# recepteur.net
KiCad netlist of a schematic drawn in EAGLE
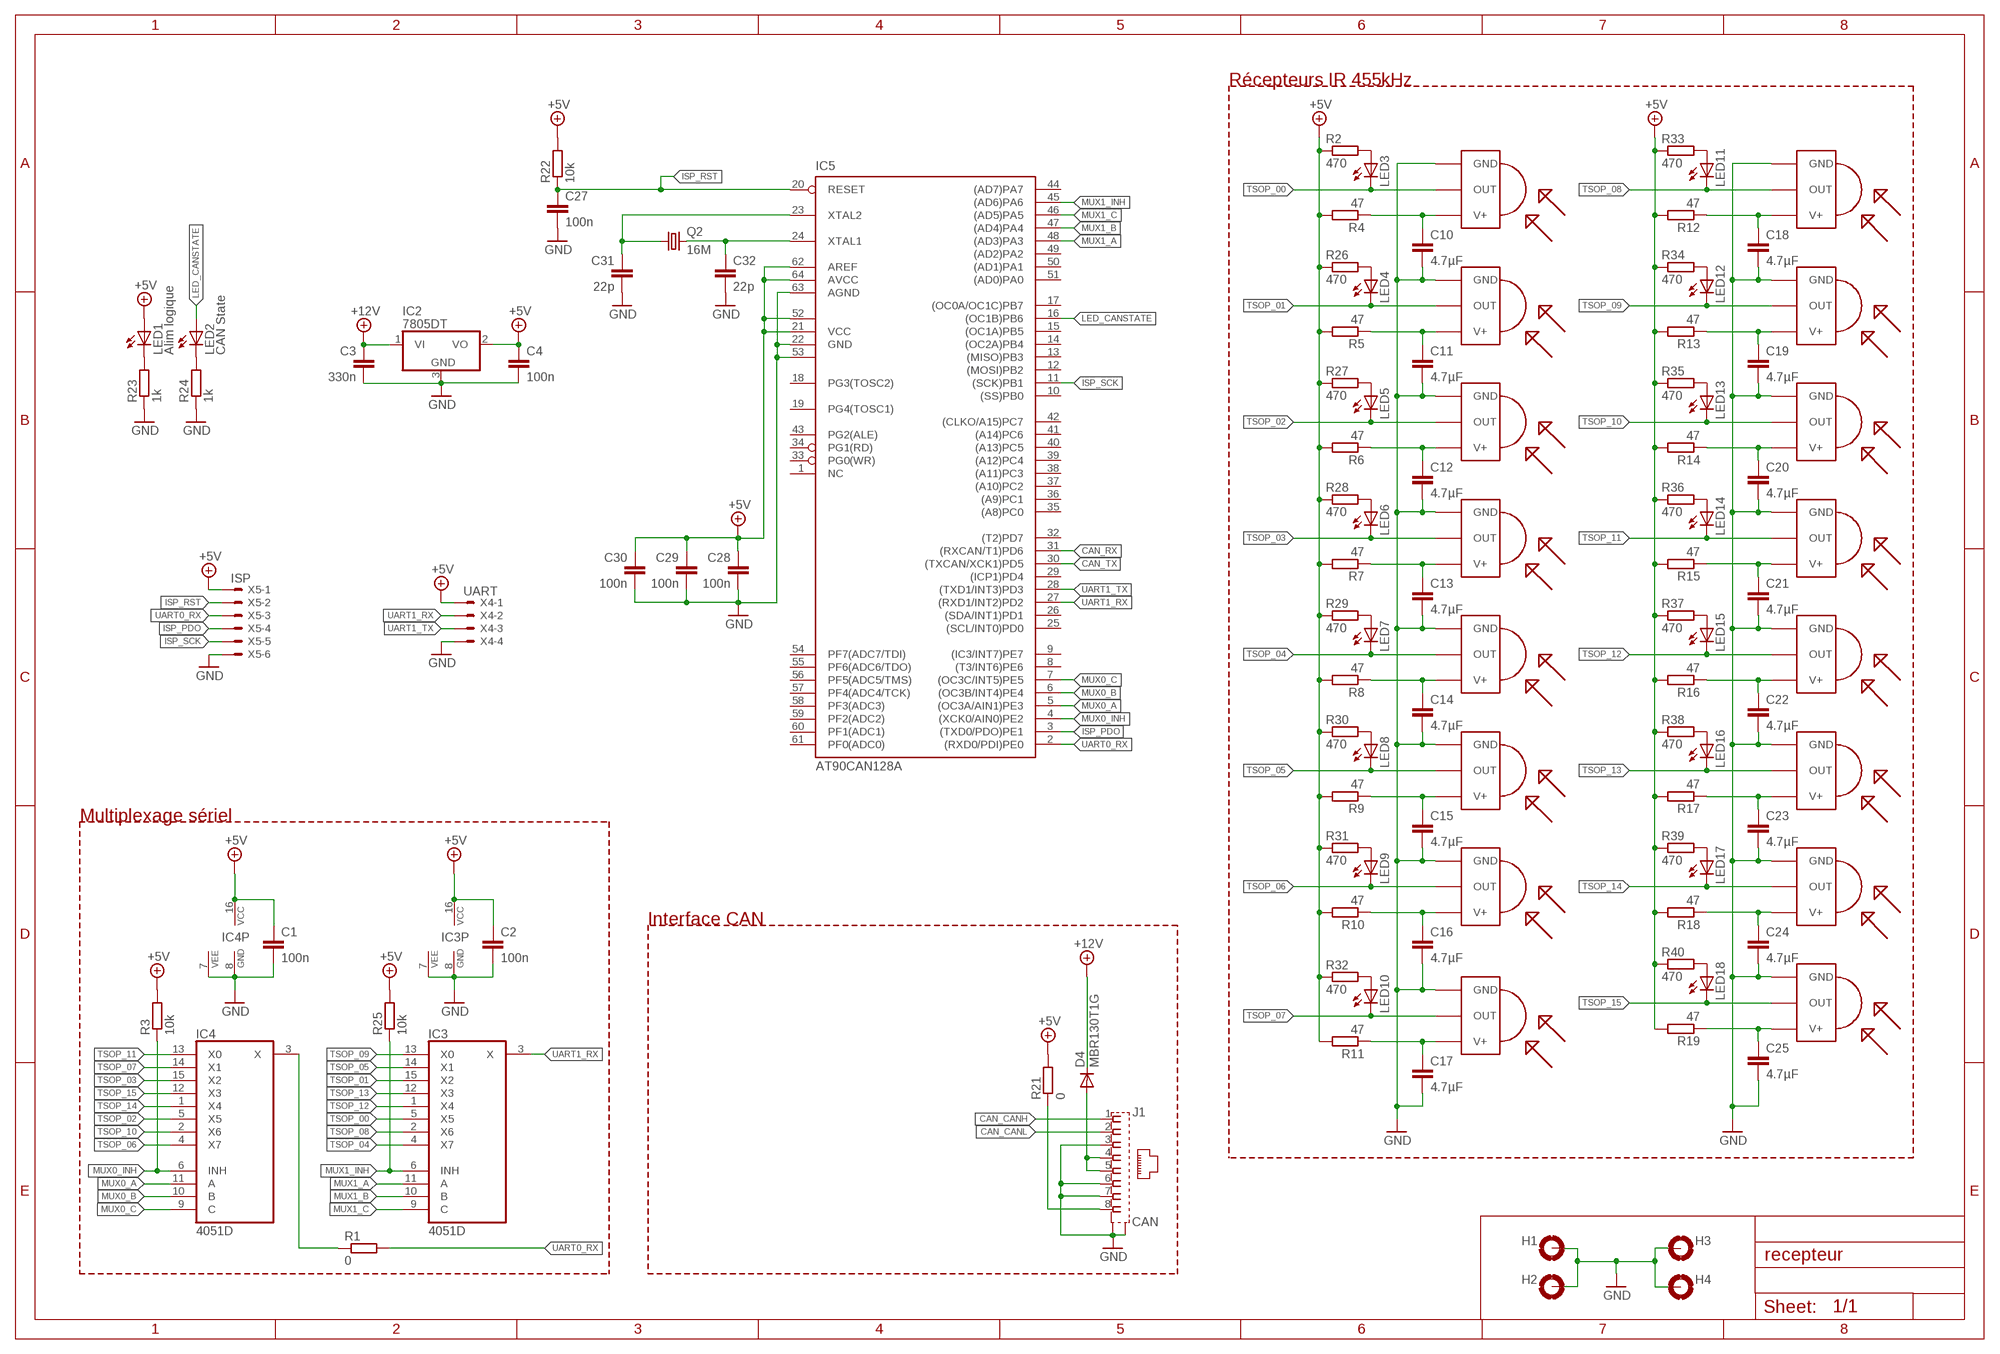
[diagram p0: schematic, sheet 1]

(export (version "E")
  (design (tool "Eeschema 10.0.6"))
  (components
    (comp (ref "C1")
      (value "100n")
      (footprint "eagle-import:C0805")
      (libsource (lib "eagle-import") (part "C-EUC0805"))
    )
    (comp (ref "C2")
      (value "100n")
      (footprint "eagle-import:C0805")
      (libsource (lib "eagle-import") (part "C-EUC0805"))
    )
    (comp (ref "C3")
      (value "330n")
      (footprint "eagle-import:C0805")
      (libsource (lib "eagle-import") (part "C-EUC0805"))
    )
    (comp (ref "C4")
      (value "100n")
      (footprint "eagle-import:C0805")
      (libsource (lib "eagle-import") (part "C-EUC0805"))
    )
    (comp (ref "C10")
      (value "4.7µF")
      (footprint "eagle-import:C0805")
      (libsource (lib "eagle-import") (part "C-EUC0805"))
    )
    (comp (ref "C11")
      (value "4.7µF")
      (footprint "eagle-import:C0805")
      (libsource (lib "eagle-import") (part "C-EUC0805"))
    )
    (comp (ref "C12")
      (value "4.7µF")
      (footprint "eagle-import:C0805")
      (libsource (lib "eagle-import") (part "C-EUC0805"))
    )
    (comp (ref "C13")
      (value "4.7µF")
      (footprint "eagle-import:C0805")
      (libsource (lib "eagle-import") (part "C-EUC0805"))
    )
    (comp (ref "C14")
      (value "4.7µF")
      (footprint "eagle-import:C0805")
      (libsource (lib "eagle-import") (part "C-EUC0805"))
    )
    (comp (ref "C15")
      (value "4.7µF")
      (footprint "eagle-import:C0805")
      (libsource (lib "eagle-import") (part "C-EUC0805"))
    )
    (comp (ref "C16")
      (value "4.7µF")
      (footprint "eagle-import:C0805")
      (libsource (lib "eagle-import") (part "C-EUC0805"))
    )
    (comp (ref "C17")
      (value "4.7µF")
      (footprint "eagle-import:C0805")
      (libsource (lib "eagle-import") (part "C-EUC0805"))
    )
    (comp (ref "C18")
      (value "4.7µF")
      (footprint "eagle-import:C0805")
      (libsource (lib "eagle-import") (part "C-EUC0805"))
    )
    (comp (ref "C19")
      (value "4.7µF")
      (footprint "eagle-import:C0805")
      (libsource (lib "eagle-import") (part "C-EUC0805"))
    )
    (comp (ref "C20")
      (value "4.7µF")
      (footprint "eagle-import:C0805")
      (libsource (lib "eagle-import") (part "C-EUC0805"))
    )
    (comp (ref "C21")
      (value "4.7µF")
      (footprint "eagle-import:C0805")
      (libsource (lib "eagle-import") (part "C-EUC0805"))
    )
    (comp (ref "C22")
      (value "4.7µF")
      (footprint "eagle-import:C0805")
      (libsource (lib "eagle-import") (part "C-EUC0805"))
    )
    (comp (ref "C23")
      (value "4.7µF")
      (footprint "eagle-import:C0805")
      (libsource (lib "eagle-import") (part "C-EUC0805"))
    )
    (comp (ref "C24")
      (value "4.7µF")
      (footprint "eagle-import:C0805")
      (libsource (lib "eagle-import") (part "C-EUC0805"))
    )
    (comp (ref "C25")
      (value "4.7µF")
      (footprint "eagle-import:C0805")
      (libsource (lib "eagle-import") (part "C-EUC0805"))
    )
    (comp (ref "C27")
      (value "100n")
      (footprint "eagle-import:C0805")
      (libsource (lib "eagle-import") (part "C-EUC0805"))
    )
    (comp (ref "C28")
      (value "100n")
      (footprint "eagle-import:C0805")
      (libsource (lib "eagle-import") (part "C-EUC0805"))
    )
    (comp (ref "C29")
      (value "100n")
      (footprint "eagle-import:C0805")
      (libsource (lib "eagle-import") (part "C-EUC0805"))
    )
    (comp (ref "C30")
      (value "100n")
      (footprint "eagle-import:C0805")
      (libsource (lib "eagle-import") (part "C-EUC0805"))
    )
    (comp (ref "C31")
      (value "22p")
      (footprint "eagle-import:C0805")
      (libsource (lib "eagle-import") (part "C-EUC0805"))
    )
    (comp (ref "C32")
      (value "22p")
      (footprint "eagle-import:C0805")
      (libsource (lib "eagle-import") (part "C-EUC0805"))
    )
    (comp (ref "D4")
      (value "MBR130T1G")
      (footprint "eagle-import:SOD123")
      (libsource (lib "eagle-import") (part "DIODE-SOD123"))
    )
    (comp (ref "H1")
      (value "MOUNT-PAD-ROUND3.0")
      (footprint "eagle-import:3,0-PAD")
      (libsource (lib "eagle-import") (part "MOUNT-PAD-ROUND3.0"))
    )
    (comp (ref "H2")
      (value "MOUNT-PAD-ROUND3.0")
      (footprint "eagle-import:3,0-PAD")
      (libsource (lib "eagle-import") (part "MOUNT-PAD-ROUND3.0"))
    )
    (comp (ref "H3")
      (value "MOUNT-PAD-ROUND3.0")
      (footprint "eagle-import:3,0-PAD")
      (libsource (lib "eagle-import") (part "MOUNT-PAD-ROUND3.0"))
    )
    (comp (ref "H4")
      (value "MOUNT-PAD-ROUND3.0")
      (footprint "eagle-import:3,0-PAD")
      (libsource (lib "eagle-import") (part "MOUNT-PAD-ROUND3.0"))
    )
    (comp (ref "IC2")
      (value "7805DT")
      (footprint "eagle-import:TO252")
      (libsource (lib "eagle-import") (part "78DT05"))
    )
    (comp (ref "IC3")
      (value "4051D")
      (footprint "eagle-import:SO16")
      (libsource (lib "eagle-import") (part "4051D"))
    )
    (comp (ref "IC4")
      (value "4051D")
      (footprint "eagle-import:SO16")
      (libsource (lib "eagle-import") (part "4051D"))
    )
    (comp (ref "IC5")
      (value "AT90CAN128A")
      (footprint "eagle-import:TQFP64")
      (libsource (lib "eagle-import") (part "AT90CAN128A"))
    )
    (comp (ref "J1")
      (value "CAN")
      (footprint "eagle-import:557969-1")
      (libsource (lib "eagle-import") (part "557969-1"))
    )
    (comp (ref "LED1")
      (value "Alim logique")
      (footprint "eagle-import:CHIP-LED0805")
      (libsource (lib "eagle-import") (part "LEDCHIP-LED0805"))
    )
    (comp (ref "LED2")
      (value "CAN State")
      (footprint "eagle-import:CHIP-LED0805")
      (libsource (lib "eagle-import") (part "LEDCHIP-LED0805"))
    )
    (comp (ref "LED3")
      (value "LEDCHIP-LED0805")
      (footprint "eagle-import:CHIP-LED0805")
      (libsource (lib "eagle-import") (part "LEDCHIP-LED0805"))
    )
    (comp (ref "LED4")
      (value "LEDCHIP-LED0805")
      (footprint "eagle-import:CHIP-LED0805")
      (libsource (lib "eagle-import") (part "LEDCHIP-LED0805"))
    )
    (comp (ref "LED5")
      (value "LEDCHIP-LED0805")
      (footprint "eagle-import:CHIP-LED0805")
      (libsource (lib "eagle-import") (part "LEDCHIP-LED0805"))
    )
    (comp (ref "LED6")
      (value "LEDCHIP-LED0805")
      (footprint "eagle-import:CHIP-LED0805")
      (libsource (lib "eagle-import") (part "LEDCHIP-LED0805"))
    )
    (comp (ref "LED7")
      (value "LEDCHIP-LED0805")
      (footprint "eagle-import:CHIP-LED0805")
      (libsource (lib "eagle-import") (part "LEDCHIP-LED0805"))
    )
    (comp (ref "LED8")
      (value "LEDCHIP-LED0805")
      (footprint "eagle-import:CHIP-LED0805")
      (libsource (lib "eagle-import") (part "LEDCHIP-LED0805"))
    )
    (comp (ref "LED9")
      (value "LEDCHIP-LED0805")
      (footprint "eagle-import:CHIP-LED0805")
      (libsource (lib "eagle-import") (part "LEDCHIP-LED0805"))
    )
    (comp (ref "LED10")
      (value "LEDCHIP-LED0805")
      (footprint "eagle-import:CHIP-LED0805")
      (libsource (lib "eagle-import") (part "LEDCHIP-LED0805"))
    )
    (comp (ref "LED11")
      (value "LEDCHIP-LED0805")
      (footprint "eagle-import:CHIP-LED0805")
      (libsource (lib "eagle-import") (part "LEDCHIP-LED0805"))
    )
    (comp (ref "LED12")
      (value "LEDCHIP-LED0805")
      (footprint "eagle-import:CHIP-LED0805")
      (libsource (lib "eagle-import") (part "LEDCHIP-LED0805"))
    )
    (comp (ref "LED13")
      (value "LEDCHIP-LED0805")
      (footprint "eagle-import:CHIP-LED0805")
      (libsource (lib "eagle-import") (part "LEDCHIP-LED0805"))
    )
    (comp (ref "LED14")
      (value "LEDCHIP-LED0805")
      (footprint "eagle-import:CHIP-LED0805")
      (libsource (lib "eagle-import") (part "LEDCHIP-LED0805"))
    )
    (comp (ref "LED15")
      (value "LEDCHIP-LED0805")
      (footprint "eagle-import:CHIP-LED0805")
      (libsource (lib "eagle-import") (part "LEDCHIP-LED0805"))
    )
    (comp (ref "LED16")
      (value "LEDCHIP-LED0805")
      (footprint "eagle-import:CHIP-LED0805")
      (libsource (lib "eagle-import") (part "LEDCHIP-LED0805"))
    )
    (comp (ref "LED17")
      (value "LEDCHIP-LED0805")
      (footprint "eagle-import:CHIP-LED0805")
      (libsource (lib "eagle-import") (part "LEDCHIP-LED0805"))
    )
    (comp (ref "LED18")
      (value "LEDCHIP-LED0805")
      (footprint "eagle-import:CHIP-LED0805")
      (libsource (lib "eagle-import") (part "LEDCHIP-LED0805"))
    )
    (comp (ref "Q2")
      (value "16M")
      (footprint "eagle-import:HC49UP")
      (libsource (lib "eagle-import") (part "CRYSTALHC49UP"))
    )
    (comp (ref "R1")
      (value "0")
      (footprint "eagle-import:R0805")
      (libsource (lib "eagle-import") (part "R-EU_R0805"))
    )
    (comp (ref "R2")
      (value "470")
      (footprint "eagle-import:R0805")
      (libsource (lib "eagle-import") (part "R-EU_R0805"))
    )
    (comp (ref "R3")
      (value "10k")
      (footprint "eagle-import:R0805")
      (libsource (lib "eagle-import") (part "R-EU_R0805"))
    )
    (comp (ref "R4")
      (value "47")
      (footprint "eagle-import:R0805")
      (libsource (lib "eagle-import") (part "R-EU_R0805"))
    )
    (comp (ref "R5")
      (value "47")
      (footprint "eagle-import:R0805")
      (libsource (lib "eagle-import") (part "R-EU_R0805"))
    )
    (comp (ref "R6")
      (value "47")
      (footprint "eagle-import:R0805")
      (libsource (lib "eagle-import") (part "R-EU_R0805"))
    )
    (comp (ref "R7")
      (value "47")
      (footprint "eagle-import:R0805")
      (libsource (lib "eagle-import") (part "R-EU_R0805"))
    )
    (comp (ref "R8")
      (value "47")
      (footprint "eagle-import:R0805")
      (libsource (lib "eagle-import") (part "R-EU_R0805"))
    )
    (comp (ref "R9")
      (value "47")
      (footprint "eagle-import:R0805")
      (libsource (lib "eagle-import") (part "R-EU_R0805"))
    )
    (comp (ref "R10")
      (value "47")
      (footprint "eagle-import:R0805")
      (libsource (lib "eagle-import") (part "R-EU_R0805"))
    )
    (comp (ref "R11")
      (value "47")
      (footprint "eagle-import:R0805")
      (libsource (lib "eagle-import") (part "R-EU_R0805"))
    )
    (comp (ref "R12")
      (value "47")
      (footprint "eagle-import:R0805")
      (libsource (lib "eagle-import") (part "R-EU_R0805"))
    )
    (comp (ref "R13")
      (value "47")
      (footprint "eagle-import:R0805")
      (libsource (lib "eagle-import") (part "R-EU_R0805"))
    )
    (comp (ref "R14")
      (value "47")
      (footprint "eagle-import:R0805")
      (libsource (lib "eagle-import") (part "R-EU_R0805"))
    )
    (comp (ref "R15")
      (value "47")
      (footprint "eagle-import:R0805")
      (libsource (lib "eagle-import") (part "R-EU_R0805"))
    )
    (comp (ref "R16")
      (value "47")
      (footprint "eagle-import:R0805")
      (libsource (lib "eagle-import") (part "R-EU_R0805"))
    )
    (comp (ref "R17")
      (value "47")
      (footprint "eagle-import:R0805")
      (libsource (lib "eagle-import") (part "R-EU_R0805"))
    )
    (comp (ref "R18")
      (value "47")
      (footprint "eagle-import:R0805")
      (libsource (lib "eagle-import") (part "R-EU_R0805"))
    )
    (comp (ref "R19")
      (value "47")
      (footprint "eagle-import:R0805")
      (libsource (lib "eagle-import") (part "R-EU_R0805"))
    )
    (comp (ref "R21")
      (value "0")
      (footprint "eagle-import:M0805")
      (libsource (lib "eagle-import") (part "R-EU_M0805"))
    )
    (comp (ref "R22")
      (value "10k")
      (footprint "eagle-import:R0805")
      (libsource (lib "eagle-import") (part "R-EU_R0805"))
    )
    (comp (ref "R23")
      (value "1k")
      (footprint "eagle-import:M0805")
      (libsource (lib "eagle-import") (part "R-EU_M0805"))
    )
    (comp (ref "R24")
      (value "1k")
      (footprint "eagle-import:M0805")
      (libsource (lib "eagle-import") (part "R-EU_M0805"))
    )
    (comp (ref "R25")
      (value "10k")
      (footprint "eagle-import:R0805")
      (libsource (lib "eagle-import") (part "R-EU_R0805"))
    )
    (comp (ref "R26")
      (value "470")
      (footprint "eagle-import:R0805")
      (libsource (lib "eagle-import") (part "R-EU_R0805"))
    )
    (comp (ref "R27")
      (value "470")
      (footprint "eagle-import:R0805")
      (libsource (lib "eagle-import") (part "R-EU_R0805"))
    )
    (comp (ref "R28")
      (value "470")
      (footprint "eagle-import:R0805")
      (libsource (lib "eagle-import") (part "R-EU_R0805"))
    )
    (comp (ref "R29")
      (value "470")
      (footprint "eagle-import:R0805")
      (libsource (lib "eagle-import") (part "R-EU_R0805"))
    )
    (comp (ref "R30")
      (value "470")
      (footprint "eagle-import:R0805")
      (libsource (lib "eagle-import") (part "R-EU_R0805"))
    )
    (comp (ref "R31")
      (value "470")
      (footprint "eagle-import:R0805")
      (libsource (lib "eagle-import") (part "R-EU_R0805"))
    )
    (comp (ref "R32")
      (value "470")
      (footprint "eagle-import:R0805")
      (libsource (lib "eagle-import") (part "R-EU_R0805"))
    )
    (comp (ref "R33")
      (value "470")
      (footprint "eagle-import:R0805")
      (libsource (lib "eagle-import") (part "R-EU_R0805"))
    )
    (comp (ref "R34")
      (value "470")
      (footprint "eagle-import:R0805")
      (libsource (lib "eagle-import") (part "R-EU_R0805"))
    )
    (comp (ref "R35")
      (value "470")
      (footprint "eagle-import:R0805")
      (libsource (lib "eagle-import") (part "R-EU_R0805"))
    )
    (comp (ref "R36")
      (value "470")
      (footprint "eagle-import:R0805")
      (libsource (lib "eagle-import") (part "R-EU_R0805"))
    )
    (comp (ref "R37")
      (value "470")
      (footprint "eagle-import:R0805")
      (libsource (lib "eagle-import") (part "R-EU_R0805"))
    )
    (comp (ref "R38")
      (value "470")
      (footprint "eagle-import:R0805")
      (libsource (lib "eagle-import") (part "R-EU_R0805"))
    )
    (comp (ref "R39")
      (value "470")
      (footprint "eagle-import:R0805")
      (libsource (lib "eagle-import") (part "R-EU_R0805"))
    )
    (comp (ref "R40")
      (value "470")
      (footprint "eagle-import:R0805")
      (libsource (lib "eagle-import") (part "R-EU_R0805"))
    )
    (comp (ref "TSOP00")
      (value "TSOP7000")
      (footprint "eagle-import:TSOP18XX")
      (libsource (lib "eagle-import") (part "TSOP1830"))
    )
    (comp (ref "TSOP01")
      (value "TSOP7000")
      (footprint "eagle-import:TSOP18XX")
      (libsource (lib "eagle-import") (part "TSOP1830"))
    )
    (comp (ref "TSOP02")
      (value "TSOP7000")
      (footprint "eagle-import:TSOP18XX")
      (libsource (lib "eagle-import") (part "TSOP1830"))
    )
    (comp (ref "TSOP03")
      (value "TSOP7000")
      (footprint "eagle-import:TSOP18XX")
      (libsource (lib "eagle-import") (part "TSOP1830"))
    )
    (comp (ref "TSOP04")
      (value "TSOP7000")
      (footprint "eagle-import:TSOP18XX")
      (libsource (lib "eagle-import") (part "TSOP1830"))
    )
    (comp (ref "TSOP05")
      (value "TSOP7000")
      (footprint "eagle-import:TSOP18XX")
      (libsource (lib "eagle-import") (part "TSOP1830"))
    )
    (comp (ref "TSOP06")
      (value "TSOP7000")
      (footprint "eagle-import:TSOP18XX")
      (libsource (lib "eagle-import") (part "TSOP1830"))
    )
    (comp (ref "TSOP07")
      (value "TSOP7000")
      (footprint "eagle-import:TSOP18XX")
      (libsource (lib "eagle-import") (part "TSOP1830"))
    )
    (comp (ref "TSOP08")
      (value "TSOP7000")
      (footprint "eagle-import:TSOP18XX")
      (libsource (lib "eagle-import") (part "TSOP1830"))
    )
    (comp (ref "TSOP09")
      (value "TSOP7000")
      (footprint "eagle-import:TSOP18XX")
      (libsource (lib "eagle-import") (part "TSOP1830"))
    )
    (comp (ref "TSOP10")
      (value "TSOP7000")
      (footprint "eagle-import:TSOP18XX")
      (libsource (lib "eagle-import") (part "TSOP1830"))
    )
    (comp (ref "TSOP11")
      (value "TSOP7000")
      (footprint "eagle-import:TSOP18XX")
      (libsource (lib "eagle-import") (part "TSOP1830"))
    )
    (comp (ref "TSOP12")
      (value "TSOP7000")
      (footprint "eagle-import:TSOP18XX")
      (libsource (lib "eagle-import") (part "TSOP1830"))
    )
    (comp (ref "TSOP13")
      (value "TSOP7000")
      (footprint "eagle-import:TSOP18XX")
      (libsource (lib "eagle-import") (part "TSOP1830"))
    )
    (comp (ref "TSOP14")
      (value "TSOP7000")
      (footprint "eagle-import:TSOP18XX")
      (libsource (lib "eagle-import") (part "TSOP1830"))
    )
    (comp (ref "TSOP15")
      (value "TSOP7000")
      (footprint "eagle-import:TSOP18XX")
      (libsource (lib "eagle-import") (part "TSOP1830"))
    )
    (comp (ref "X4")
      (value "UART")
      (footprint "eagle-import:53261-04")
      (libsource (lib "eagle-import") (part "53?-04261"))
    )
    (comp (ref "X5")
      (value "ISP")
      (footprint "eagle-import:53261-06")
      (libsource (lib "eagle-import") (part "53?-06261"))
    )
  )
  (nets
    (net (code "1") (name "+5V") (class "Default")
      (node (ref "C1") (pin "1") (pinfunction "1_1") (pintype "passive"))
      (node (ref "C2") (pin "1") (pinfunction "1_1") (pintype "passive"))
      (node (ref "C28") (pin "1") (pinfunction "1_1") (pintype "passive"))
      (node (ref "C29") (pin "1") (pinfunction "1_1") (pintype "passive"))
      (node (ref "C30") (pin "1") (pinfunction "1_1") (pintype "passive"))
      (node (ref "C4") (pin "1") (pinfunction "1_1") (pintype "passive"))
      (node (ref "IC2") (pin "2") (pinfunction "VO_2") (pintype "passive"))
      (node (ref "IC3") (pin "16") (pinfunction "VCC_16") (pintype "power_in"))
      (node (ref "IC4") (pin "16") (pinfunction "VCC_16") (pintype "power_in"))
      (node (ref "IC5") (pin "21") (pinfunction "VCC_21") (pintype "power_in"))
      (node (ref "IC5") (pin "52") (pinfunction "VCC1_52") (pintype "power_in"))
      (node (ref "IC5") (pin "62") (pinfunction "AREF_62") (pintype "bidirectional"))
      (node (ref "IC5") (pin "64") (pinfunction "AVCC_64") (pintype "bidirectional"))
      (node (ref "LED1") (pin "A") (pinfunction "A_A") (pintype "passive"))
      (node (ref "R10") (pin "2") (pinfunction "2_2") (pintype "passive"))
      (node (ref "R11") (pin "2") (pinfunction "2_2") (pintype "passive"))
      (node (ref "R12") (pin "2") (pinfunction "2_2") (pintype "passive"))
      (node (ref "R13") (pin "2") (pinfunction "2_2") (pintype "passive"))
      (node (ref "R14") (pin "2") (pinfunction "2_2") (pintype "passive"))
      (node (ref "R15") (pin "2") (pinfunction "2_2") (pintype "passive"))
      (node (ref "R16") (pin "2") (pinfunction "2_2") (pintype "passive"))
      (node (ref "R17") (pin "2") (pinfunction "2_2") (pintype "passive"))
      (node (ref "R18") (pin "2") (pinfunction "2_2") (pintype "passive"))
      (node (ref "R19") (pin "2") (pinfunction "2_2") (pintype "passive"))
      (node (ref "R2") (pin "1") (pinfunction "1_1") (pintype "passive"))
      (node (ref "R21") (pin "2") (pinfunction "2_2") (pintype "passive"))
      (node (ref "R22") (pin "2") (pinfunction "2_2") (pintype "passive"))
      (node (ref "R25") (pin "2") (pinfunction "2_2") (pintype "passive"))
      (node (ref "R26") (pin "1") (pinfunction "1_1") (pintype "passive"))
      (node (ref "R27") (pin "1") (pinfunction "1_1") (pintype "passive"))
      (node (ref "R28") (pin "1") (pinfunction "1_1") (pintype "passive"))
      (node (ref "R29") (pin "1") (pinfunction "1_1") (pintype "passive"))
      (node (ref "R3") (pin "2") (pinfunction "2_2") (pintype "passive"))
      (node (ref "R30") (pin "1") (pinfunction "1_1") (pintype "passive"))
      (node (ref "R31") (pin "1") (pinfunction "1_1") (pintype "passive"))
      (node (ref "R32") (pin "1") (pinfunction "1_1") (pintype "passive"))
      (node (ref "R33") (pin "1") (pinfunction "1_1") (pintype "passive"))
      (node (ref "R34") (pin "1") (pinfunction "1_1") (pintype "passive"))
      (node (ref "R35") (pin "1") (pinfunction "1_1") (pintype "passive"))
      (node (ref "R36") (pin "1") (pinfunction "1_1") (pintype "passive"))
      (node (ref "R37") (pin "1") (pinfunction "1_1") (pintype "passive"))
      (node (ref "R38") (pin "1") (pinfunction "1_1") (pintype "passive"))
      (node (ref "R39") (pin "1") (pinfunction "1_1") (pintype "passive"))
      (node (ref "R4") (pin "2") (pinfunction "2_2") (pintype "passive"))
      (node (ref "R40") (pin "1") (pinfunction "1_1") (pintype "passive"))
      (node (ref "R5") (pin "2") (pinfunction "2_2") (pintype "passive"))
      (node (ref "R6") (pin "2") (pinfunction "2_2") (pintype "passive"))
      (node (ref "R7") (pin "2") (pinfunction "2_2") (pintype "passive"))
      (node (ref "R8") (pin "2") (pinfunction "2_2") (pintype "passive"))
      (node (ref "R9") (pin "2") (pinfunction "2_2") (pintype "passive"))
      (node (ref "X4") (pin "1") (pinfunction "S_1") (pintype "passive"))
      (node (ref "X5") (pin "1") (pinfunction "S_1") (pintype "passive"))
    )
    (net (code "2") (name "+12V") (class "Default")
      (node (ref "C3") (pin "1") (pinfunction "1_1") (pintype "passive"))
      (node (ref "D4") (pin "C") (pinfunction "C_C") (pintype "passive"))
      (node (ref "IC2") (pin "1") (pinfunction "VI_1") (pintype "input"))
    )
    (net (code "3") (name "CAN_CANH") (class "Default")
      (node (ref "J1") (pin "1") (pinfunction "1_1") (pintype "passive"))
    )
    (net (code "4") (name "CAN_CANL") (class "Default")
      (node (ref "J1") (pin "2") (pinfunction "2_2") (pintype "passive"))
    )
    (net (code "5") (name "CAN_RX") (class "Default")
      (node (ref "IC5") (pin "31") (pinfunction "(RXCAN/T1)PD6_31") (pintype "bidirectional"))
    )
    (net (code "6") (name "CAN_TX") (class "Default")
      (node (ref "IC5") (pin "30") (pinfunction "(TXCAN/XCK1)PD5_30") (pintype "bidirectional"))
    )
    (net (code "7") (name "GND") (class "Default")
      (node (ref "C1") (pin "2") (pinfunction "2_2") (pintype "passive"))
      (node (ref "C10") (pin "2") (pinfunction "2_2") (pintype "passive"))
      (node (ref "C11") (pin "2") (pinfunction "2_2") (pintype "passive"))
      (node (ref "C12") (pin "2") (pinfunction "2_2") (pintype "passive"))
      (node (ref "C13") (pin "2") (pinfunction "2_2") (pintype "passive"))
      (node (ref "C14") (pin "2") (pinfunction "2_2") (pintype "passive"))
      (node (ref "C15") (pin "2") (pinfunction "2_2") (pintype "passive"))
      (node (ref "C16") (pin "2") (pinfunction "2_2") (pintype "passive"))
      (node (ref "C17") (pin "2") (pinfunction "2_2") (pintype "passive"))
      (node (ref "C18") (pin "2") (pinfunction "2_2") (pintype "passive"))
      (node (ref "C19") (pin "2") (pinfunction "2_2") (pintype "passive"))
      (node (ref "C2") (pin "2") (pinfunction "2_2") (pintype "passive"))
      (node (ref "C20") (pin "2") (pinfunction "2_2") (pintype "passive"))
      (node (ref "C21") (pin "2") (pinfunction "2_2") (pintype "passive"))
      (node (ref "C22") (pin "2") (pinfunction "2_2") (pintype "passive"))
      (node (ref "C23") (pin "2") (pinfunction "2_2") (pintype "passive"))
      (node (ref "C24") (pin "2") (pinfunction "2_2") (pintype "passive"))
      (node (ref "C25") (pin "2") (pinfunction "2_2") (pintype "passive"))
      (node (ref "C27") (pin "2") (pinfunction "2_2") (pintype "passive"))
      (node (ref "C28") (pin "2") (pinfunction "2_2") (pintype "passive"))
      (node (ref "C29") (pin "2") (pinfunction "2_2") (pintype "passive"))
      (node (ref "C3") (pin "2") (pinfunction "2_2") (pintype "passive"))
      (node (ref "C30") (pin "2") (pinfunction "2_2") (pintype "passive"))
      (node (ref "C31") (pin "2") (pinfunction "2_2") (pintype "passive"))
      (node (ref "C32") (pin "2") (pinfunction "2_2") (pintype "passive"))
      (node (ref "C4") (pin "2") (pinfunction "2_2") (pintype "passive"))
      (node (ref "H1") (pin "B3,0") (pinfunction "MOUNT_B3,0") (pintype "passive"))
      (node (ref "H2") (pin "B3,0") (pinfunction "MOUNT_B3,0") (pintype "passive"))
      (node (ref "H3") (pin "B3,0") (pinfunction "MOUNT_B3,0") (pintype "passive"))
      (node (ref "H4") (pin "B3,0") (pinfunction "MOUNT_B3,0") (pintype "passive"))
      (node (ref "IC2") (pin "3") (pinfunction "GND_3") (pintype "passive"))
      (node (ref "IC3") (pin "7") (pinfunction "VEE_7") (pintype "power_in"))
      (node (ref "IC3") (pin "8") (pinfunction "GND_8") (pintype "power_in"))
      (node (ref "IC4") (pin "7") (pinfunction "VEE_7") (pintype "power_in"))
      (node (ref "IC4") (pin "8") (pinfunction "GND_8") (pintype "power_in"))
      (node (ref "IC5") (pin "22") (pinfunction "GND_22") (pintype "power_in"))
      (node (ref "IC5") (pin "53") (pinfunction "GND1_53") (pintype "power_in"))
      (node (ref "IC5") (pin "63") (pinfunction "AGND_63") (pintype "bidirectional"))
      (node (ref "J1") (pin "3") (pinfunction "3_3") (pintype "passive"))
      (node (ref "J1") (pin "6") (pinfunction "6_6") (pintype "passive"))
      (node (ref "J1") (pin "7") (pinfunction "7_7") (pintype "passive"))
      (node (ref "J1") (pin "G1") (pinfunction "S2_G1") (pintype "passive"))
      (node (ref "J1") (pin "G2") (pinfunction "S1_G2") (pintype "passive"))
      (node (ref "R23") (pin "1") (pinfunction "1_1") (pintype "passive"))
      (node (ref "R24") (pin "1") (pinfunction "1_1") (pintype "passive"))
      (node (ref "TSOP00") (pin "GND") (pinfunction "GND_GND") (pintype "bidirectional"))
      (node (ref "TSOP01") (pin "GND") (pinfunction "GND_GND") (pintype "bidirectional"))
      (node (ref "TSOP02") (pin "GND") (pinfunction "GND_GND") (pintype "bidirectional"))
      (node (ref "TSOP03") (pin "GND") (pinfunction "GND_GND") (pintype "bidirectional"))
      (node (ref "TSOP04") (pin "GND") (pinfunction "GND_GND") (pintype "bidirectional"))
      (node (ref "TSOP05") (pin "GND") (pinfunction "GND_GND") (pintype "bidirectional"))
      (node (ref "TSOP06") (pin "GND") (pinfunction "GND_GND") (pintype "bidirectional"))
      (node (ref "TSOP07") (pin "GND") (pinfunction "GND_GND") (pintype "bidirectional"))
      (node (ref "TSOP08") (pin "GND") (pinfunction "GND_GND") (pintype "bidirectional"))
      (node (ref "TSOP09") (pin "GND") (pinfunction "GND_GND") (pintype "bidirectional"))
      (node (ref "TSOP10") (pin "GND") (pinfunction "GND_GND") (pintype "bidirectional"))
      (node (ref "TSOP11") (pin "GND") (pinfunction "GND_GND") (pintype "bidirectional"))
      (node (ref "TSOP12") (pin "GND") (pinfunction "GND_GND") (pintype "bidirectional"))
      (node (ref "TSOP13") (pin "GND") (pinfunction "GND_GND") (pintype "bidirectional"))
      (node (ref "TSOP14") (pin "GND") (pinfunction "GND_GND") (pintype "bidirectional"))
      (node (ref "TSOP15") (pin "GND") (pinfunction "GND_GND") (pintype "bidirectional"))
      (node (ref "X4") (pin "4") (pinfunction "S_4") (pintype "passive"))
      (node (ref "X5") (pin "6") (pinfunction "S_6") (pintype "passive"))
    )
    (net (code "8") (name "ISP_PDO") (class "Default")
      (node (ref "IC5") (pin "3") (pinfunction "(TXD0/PDO)PE1_3") (pintype "bidirectional"))
      (node (ref "X5") (pin "4") (pinfunction "S_4") (pintype "passive"))
    )
    (net (code "9") (name "ISP_RST") (class "Default")
      (node (ref "C27") (pin "1") (pinfunction "1_1") (pintype "passive"))
      (node (ref "IC5") (pin "20") (pinfunction "RESET_20") (pintype "input"))
      (node (ref "R22") (pin "1") (pinfunction "1_1") (pintype "passive"))
      (node (ref "X5") (pin "2") (pinfunction "S_2") (pintype "passive"))
    )
    (net (code "10") (name "ISP_SCK") (class "Default")
      (node (ref "IC5") (pin "11") (pinfunction "(SCK)PB1_11") (pintype "bidirectional"))
      (node (ref "X5") (pin "5") (pinfunction "S_5") (pintype "passive"))
    )
    (net (code "11") (name "LED_CANSTATE") (class "Default")
      (node (ref "IC5") (pin "16") (pinfunction "(OC1B)PB6_16") (pintype "bidirectional"))
      (node (ref "LED2") (pin "A") (pinfunction "A_A") (pintype "passive"))
    )
    (net (code "12") (name "MUX0_A") (class "Default")
      (node (ref "IC4") (pin "11") (pinfunction "A_11") (pintype "input"))
      (node (ref "IC5") (pin "5") (pinfunction "(OC3A/AIN1)PE3_5") (pintype "bidirectional"))
    )
    (net (code "13") (name "MUX0_B") (class "Default")
      (node (ref "IC4") (pin "10") (pinfunction "B_10") (pintype "input"))
      (node (ref "IC5") (pin "6") (pinfunction "(OC3B/INT4)PE4_6") (pintype "bidirectional"))
    )
    (net (code "14") (name "MUX0_C") (class "Default")
      (node (ref "IC4") (pin "9") (pinfunction "C_9") (pintype "input"))
      (node (ref "IC5") (pin "7") (pinfunction "(OC3C/INT5)PE5_7") (pintype "bidirectional"))
    )
    (net (code "15") (name "MUX0_INH") (class "Default")
      (node (ref "IC4") (pin "6") (pinfunction "INH_6") (pintype "input"))
      (node (ref "IC5") (pin "4") (pinfunction "(XCK0/AIN0)PE2_4") (pintype "bidirectional"))
      (node (ref "R3") (pin "1") (pinfunction "1_1") (pintype "passive"))
    )
    (net (code "16") (name "MUX1_A") (class "Default")
      (node (ref "IC3") (pin "11") (pinfunction "A_11") (pintype "input"))
      (node (ref "IC5") (pin "48") (pinfunction "(AD3)PA3_48") (pintype "bidirectional"))
    )
    (net (code "17") (name "MUX1_B") (class "Default")
      (node (ref "IC3") (pin "10") (pinfunction "B_10") (pintype "input"))
      (node (ref "IC5") (pin "47") (pinfunction "(AD4)PA4_47") (pintype "bidirectional"))
    )
    (net (code "18") (name "MUX1_C") (class "Default")
      (node (ref "IC3") (pin "9") (pinfunction "C_9") (pintype "input"))
      (node (ref "IC5") (pin "46") (pinfunction "(AD5)PA5_46") (pintype "bidirectional"))
    )
    (net (code "19") (name "MUX1_INH") (class "Default")
      (node (ref "IC3") (pin "6") (pinfunction "INH_6") (pintype "input"))
      (node (ref "IC5") (pin "45") (pinfunction "(AD6)PA6_45") (pintype "bidirectional"))
      (node (ref "R25") (pin "1") (pinfunction "1_1") (pintype "passive"))
    )
    (net (code "20") (name "Net-(D4-PadA)") (class "Default")
      (node (ref "D4") (pin "A") (pinfunction "A_A") (pintype "passive"))
      (node (ref "J1") (pin "4") (pinfunction "4_4") (pintype "passive"))
      (node (ref "J1") (pin "5") (pinfunction "5_5") (pintype "passive"))
    )
    (net (code "21") (name "Net-(IC4A-X)") (class "Default")
      (node (ref "IC4") (pin "3") (pinfunction "X_3") (pintype "bidirectional"))
      (node (ref "R1") (pin "1") (pinfunction "1_1") (pintype "passive"))
    )
    (net (code "22") (name "Net-(IC5-XTAL1)") (class "Default")
      (node (ref "C32") (pin "1") (pinfunction "1_1") (pintype "passive"))
      (node (ref "IC5") (pin "24") (pinfunction "XTAL1_24") (pintype "bidirectional"))
      (node (ref "Q2") (pin "2") (pinfunction "2_2") (pintype "passive"))
    )
    (net (code "23") (name "Net-(IC5-XTAL2)") (class "Default")
      (node (ref "C31") (pin "1") (pinfunction "1_1") (pintype "passive"))
      (node (ref "IC5") (pin "23") (pinfunction "XTAL2_23") (pintype "bidirectional"))
      (node (ref "Q2") (pin "1") (pinfunction "1_1") (pintype "passive"))
    )
    (net (code "24") (name "Net-(J1-Pad8)") (class "Default")
      (node (ref "J1") (pin "8") (pinfunction "8_8") (pintype "passive"))
      (node (ref "R21") (pin "1") (pinfunction "1_1") (pintype "passive"))
    )
    (net (code "25") (name "Net-(LED1-PadC)") (class "Default")
      (node (ref "LED1") (pin "C") (pinfunction "C_C") (pintype "passive"))
      (node (ref "R23") (pin "2") (pinfunction "2_2") (pintype "passive"))
    )
    (net (code "26") (name "Net-(LED2-PadC)") (class "Default")
      (node (ref "LED2") (pin "C") (pinfunction "C_C") (pintype "passive"))
      (node (ref "R24") (pin "2") (pinfunction "2_2") (pintype "passive"))
    )
    (net (code "27") (name "Net-(LED3-PadA)") (class "Default")
      (node (ref "LED3") (pin "A") (pinfunction "A_A") (pintype "passive"))
      (node (ref "R2") (pin "2") (pinfunction "2_2") (pintype "passive"))
    )
    (net (code "28") (name "Net-(LED4-PadA)") (class "Default")
      (node (ref "LED4") (pin "A") (pinfunction "A_A") (pintype "passive"))
      (node (ref "R26") (pin "2") (pinfunction "2_2") (pintype "passive"))
    )
    (net (code "29") (name "Net-(LED5-PadA)") (class "Default")
      (node (ref "LED5") (pin "A") (pinfunction "A_A") (pintype "passive"))
      (node (ref "R27") (pin "2") (pinfunction "2_2") (pintype "passive"))
    )
    (net (code "30") (name "Net-(LED6-PadA)") (class "Default")
      (node (ref "LED6") (pin "A") (pinfunction "A_A") (pintype "passive"))
      (node (ref "R28") (pin "2") (pinfunction "2_2") (pintype "passive"))
    )
    (net (code "31") (name "Net-(LED7-PadA)") (class "Default")
      (node (ref "LED7") (pin "A") (pinfunction "A_A") (pintype "passive"))
      (node (ref "R29") (pin "2") (pinfunction "2_2") (pintype "passive"))
    )
    (net (code "32") (name "Net-(LED8-PadA)") (class "Default")
      (node (ref "LED8") (pin "A") (pinfunction "A_A") (pintype "passive"))
      (node (ref "R30") (pin "2") (pinfunction "2_2") (pintype "passive"))
    )
    (net (code "33") (name "Net-(LED9-PadA)") (class "Default")
      (node (ref "LED9") (pin "A") (pinfunction "A_A") (pintype "passive"))
      (node (ref "R31") (pin "2") (pinfunction "2_2") (pintype "passive"))
    )
    (net (code "34") (name "Net-(LED10-PadA)") (class "Default")
      (node (ref "LED10") (pin "A") (pinfunction "A_A") (pintype "passive"))
      (node (ref "R32") (pin "2") (pinfunction "2_2") (pintype "passive"))
    )
    (net (code "35") (name "Net-(LED11-PadA)") (class "Default")
      (node (ref "LED11") (pin "A") (pinfunction "A_A") (pintype "passive"))
      (node (ref "R33") (pin "2") (pinfunction "2_2") (pintype "passive"))
    )
    (net (code "36") (name "Net-(LED12-PadA)") (class "Default")
      (node (ref "LED12") (pin "A") (pinfunction "A_A") (pintype "passive"))
      (node (ref "R34") (pin "2") (pinfunction "2_2") (pintype "passive"))
    )
    (net (code "37") (name "Net-(LED13-PadA)") (class "Default")
      (node (ref "LED13") (pin "A") (pinfunction "A_A") (pintype "passive"))
      (node (ref "R35") (pin "2") (pinfunction "2_2") (pintype "passive"))
    )
    (net (code "38") (name "Net-(LED14-PadA)") (class "Default")
      (node (ref "LED14") (pin "A") (pinfunction "A_A") (pintype "passive"))
      (node (ref "R36") (pin "2") (pinfunction "2_2") (pintype "passive"))
    )
    (net (code "39") (name "Net-(LED15-PadA)") (class "Default")
      (node (ref "LED15") (pin "A") (pinfunction "A_A") (pintype "passive"))
      (node (ref "R37") (pin "2") (pinfunction "2_2") (pintype "passive"))
    )
    (net (code "40") (name "Net-(LED16-PadA)") (class "Default")
      (node (ref "LED16") (pin "A") (pinfunction "A_A") (pintype "passive"))
      (node (ref "R38") (pin "2") (pinfunction "2_2") (pintype "passive"))
    )
    (net (code "41") (name "Net-(LED17-PadA)") (class "Default")
      (node (ref "LED17") (pin "A") (pinfunction "A_A") (pintype "passive"))
      (node (ref "R39") (pin "2") (pinfunction "2_2") (pintype "passive"))
    )
    (net (code "42") (name "Net-(LED18-PadA)") (class "Default")
      (node (ref "LED18") (pin "A") (pinfunction "A_A") (pintype "passive"))
      (node (ref "R40") (pin "2") (pinfunction "2_2") (pintype "passive"))
    )
    (net (code "43") (name "Net-(TSOP00-V+)") (class "Default")
      (node (ref "C10") (pin "1") (pinfunction "1_1") (pintype "passive"))
      (node (ref "R4") (pin "1") (pinfunction "1_1") (pintype "passive"))
      (node (ref "TSOP00") (pin "VCC") (pinfunction "V+_VCC") (pintype "bidirectional"))
    )
    (net (code "44") (name "Net-(TSOP01-V+)") (class "Default")
      (node (ref "C11") (pin "1") (pinfunction "1_1") (pintype "passive"))
      (node (ref "R5") (pin "1") (pinfunction "1_1") (pintype "passive"))
      (node (ref "TSOP01") (pin "VCC") (pinfunction "V+_VCC") (pintype "bidirectional"))
    )
    (net (code "45") (name "Net-(TSOP02-V+)") (class "Default")
      (node (ref "C12") (pin "1") (pinfunction "1_1") (pintype "passive"))
      (node (ref "R6") (pin "1") (pinfunction "1_1") (pintype "passive"))
      (node (ref "TSOP02") (pin "VCC") (pinfunction "V+_VCC") (pintype "bidirectional"))
    )
    (net (code "46") (name "Net-(TSOP03-V+)") (class "Default")
      (node (ref "C13") (pin "1") (pinfunction "1_1") (pintype "passive"))
      (node (ref "R7") (pin "1") (pinfunction "1_1") (pintype "passive"))
      (node (ref "TSOP03") (pin "VCC") (pinfunction "V+_VCC") (pintype "bidirectional"))
    )
    (net (code "47") (name "Net-(TSOP04-V+)") (class "Default")
      (node (ref "C14") (pin "1") (pinfunction "1_1") (pintype "passive"))
      (node (ref "R8") (pin "1") (pinfunction "1_1") (pintype "passive"))
      (node (ref "TSOP04") (pin "VCC") (pinfunction "V+_VCC") (pintype "bidirectional"))
    )
    (net (code "48") (name "Net-(TSOP05-V+)") (class "Default")
      (node (ref "C15") (pin "1") (pinfunction "1_1") (pintype "passive"))
      (node (ref "R9") (pin "1") (pinfunction "1_1") (pintype "passive"))
      (node (ref "TSOP05") (pin "VCC") (pinfunction "V+_VCC") (pintype "bidirectional"))
    )
    (net (code "49") (name "Net-(TSOP06-V+)") (class "Default")
      (node (ref "C16") (pin "1") (pinfunction "1_1") (pintype "passive"))
      (node (ref "R10") (pin "1") (pinfunction "1_1") (pintype "passive"))
      (node (ref "TSOP06") (pin "VCC") (pinfunction "V+_VCC") (pintype "bidirectional"))
    )
    (net (code "50") (name "Net-(TSOP07-V+)") (class "Default")
      (node (ref "C17") (pin "1") (pinfunction "1_1") (pintype "passive"))
      (node (ref "R11") (pin "1") (pinfunction "1_1") (pintype "passive"))
      (node (ref "TSOP07") (pin "VCC") (pinfunction "V+_VCC") (pintype "bidirectional"))
    )
    (net (code "51") (name "Net-(TSOP08-V+)") (class "Default")
      (node (ref "C18") (pin "1") (pinfunction "1_1") (pintype "passive"))
      (node (ref "R12") (pin "1") (pinfunction "1_1") (pintype "passive"))
      (node (ref "TSOP08") (pin "VCC") (pinfunction "V+_VCC") (pintype "bidirectional"))
    )
    (net (code "52") (name "Net-(TSOP09-V+)") (class "Default")
      (node (ref "C19") (pin "1") (pinfunction "1_1") (pintype "passive"))
      (node (ref "R13") (pin "1") (pinfunction "1_1") (pintype "passive"))
      (node (ref "TSOP09") (pin "VCC") (pinfunction "V+_VCC") (pintype "bidirectional"))
    )
    (net (code "53") (name "Net-(TSOP10-V+)") (class "Default")
      (node (ref "C20") (pin "1") (pinfunction "1_1") (pintype "passive"))
      (node (ref "R14") (pin "1") (pinfunction "1_1") (pintype "passive"))
      (node (ref "TSOP10") (pin "VCC") (pinfunction "V+_VCC") (pintype "bidirectional"))
    )
    (net (code "54") (name "Net-(TSOP11-V+)") (class "Default")
      (node (ref "C21") (pin "1") (pinfunction "1_1") (pintype "passive"))
      (node (ref "R15") (pin "1") (pinfunction "1_1") (pintype "passive"))
      (node (ref "TSOP11") (pin "VCC") (pinfunction "V+_VCC") (pintype "bidirectional"))
    )
    (net (code "55") (name "Net-(TSOP12-V+)") (class "Default")
      (node (ref "C22") (pin "1") (pinfunction "1_1") (pintype "passive"))
      (node (ref "R16") (pin "1") (pinfunction "1_1") (pintype "passive"))
      (node (ref "TSOP12") (pin "VCC") (pinfunction "V+_VCC") (pintype "bidirectional"))
    )
    (net (code "56") (name "Net-(TSOP13-V+)") (class "Default")
      (node (ref "C23") (pin "1") (pinfunction "1_1") (pintype "passive"))
      (node (ref "R17") (pin "1") (pinfunction "1_1") (pintype "passive"))
      (node (ref "TSOP13") (pin "VCC") (pinfunction "V+_VCC") (pintype "bidirectional"))
    )
    (net (code "57") (name "Net-(TSOP14-V+)") (class "Default")
      (node (ref "C24") (pin "1") (pinfunction "1_1") (pintype "passive"))
      (node (ref "R18") (pin "1") (pinfunction "1_1") (pintype "passive"))
      (node (ref "TSOP14") (pin "VCC") (pinfunction "V+_VCC") (pintype "bidirectional"))
    )
    (net (code "58") (name "Net-(TSOP15-V+)") (class "Default")
      (node (ref "C25") (pin "1") (pinfunction "1_1") (pintype "passive"))
      (node (ref "R19") (pin "1") (pinfunction "1_1") (pintype "passive"))
      (node (ref "TSOP15") (pin "VCC") (pinfunction "V+_VCC") (pintype "bidirectional"))
    )
    (net (code "59") (name "TSOP_00") (class "Default")
      (node (ref "IC3") (pin "5") (pinfunction "X5_5") (pintype "bidirectional"))
      (node (ref "LED3") (pin "C") (pinfunction "C_C") (pintype "passive"))
      (node (ref "TSOP00") (pin "OUT") (pinfunction "OUT_OUT") (pintype "bidirectional"))
    )
    (net (code "60") (name "TSOP_01") (class "Default")
      (node (ref "IC3") (pin "15") (pinfunction "X2_15") (pintype "bidirectional"))
      (node (ref "LED4") (pin "C") (pinfunction "C_C") (pintype "passive"))
      (node (ref "TSOP01") (pin "OUT") (pinfunction "OUT_OUT") (pintype "bidirectional"))
    )
    (net (code "61") (name "TSOP_02") (class "Default")
      (node (ref "IC4") (pin "5") (pinfunction "X5_5") (pintype "bidirectional"))
      (node (ref "LED5") (pin "C") (pinfunction "C_C") (pintype "passive"))
      (node (ref "TSOP02") (pin "OUT") (pinfunction "OUT_OUT") (pintype "bidirectional"))
    )
    (net (code "62") (name "TSOP_03") (class "Default")
      (node (ref "IC4") (pin "15") (pinfunction "X2_15") (pintype "bidirectional"))
      (node (ref "LED6") (pin "C") (pinfunction "C_C") (pintype "passive"))
      (node (ref "TSOP03") (pin "OUT") (pinfunction "OUT_OUT") (pintype "bidirectional"))
    )
    (net (code "63") (name "TSOP_04") (class "Default")
      (node (ref "IC3") (pin "4") (pinfunction "X7_4") (pintype "bidirectional"))
      (node (ref "LED7") (pin "C") (pinfunction "C_C") (pintype "passive"))
      (node (ref "TSOP04") (pin "OUT") (pinfunction "OUT_OUT") (pintype "bidirectional"))
    )
    (net (code "64") (name "TSOP_05") (class "Default")
      (node (ref "IC3") (pin "14") (pinfunction "X1_14") (pintype "bidirectional"))
      (node (ref "LED8") (pin "C") (pinfunction "C_C") (pintype "passive"))
      (node (ref "TSOP05") (pin "OUT") (pinfunction "OUT_OUT") (pintype "bidirectional"))
    )
    (net (code "65") (name "TSOP_06") (class "Default")
      (node (ref "IC4") (pin "4") (pinfunction "X7_4") (pintype "bidirectional"))
      (node (ref "LED9") (pin "C") (pinfunction "C_C") (pintype "passive"))
      (node (ref "TSOP06") (pin "OUT") (pinfunction "OUT_OUT") (pintype "bidirectional"))
    )
    (net (code "66") (name "TSOP_07") (class "Default")
      (node (ref "IC4") (pin "14") (pinfunction "X1_14") (pintype "bidirectional"))
      (node (ref "LED10") (pin "C") (pinfunction "C_C") (pintype "passive"))
      (node (ref "TSOP07") (pin "OUT") (pinfunction "OUT_OUT") (pintype "bidirectional"))
    )
    (net (code "67") (name "TSOP_08") (class "Default")
      (node (ref "IC3") (pin "2") (pinfunction "X6_2") (pintype "bidirectional"))
      (node (ref "LED11") (pin "C") (pinfunction "C_C") (pintype "passive"))
      (node (ref "TSOP08") (pin "OUT") (pinfunction "OUT_OUT") (pintype "bidirectional"))
    )
    (net (code "68") (name "TSOP_09") (class "Default")
      (node (ref "IC3") (pin "13") (pinfunction "X0_13") (pintype "bidirectional"))
      (node (ref "LED12") (pin "C") (pinfunction "C_C") (pintype "passive"))
      (node (ref "TSOP09") (pin "OUT") (pinfunction "OUT_OUT") (pintype "bidirectional"))
    )
    (net (code "69") (name "TSOP_10") (class "Default")
      (node (ref "IC4") (pin "2") (pinfunction "X6_2") (pintype "bidirectional"))
      (node (ref "LED13") (pin "C") (pinfunction "C_C") (pintype "passive"))
      (node (ref "TSOP10") (pin "OUT") (pinfunction "OUT_OUT") (pintype "bidirectional"))
    )
    (net (code "70") (name "TSOP_11") (class "Default")
      (node (ref "IC4") (pin "13") (pinfunction "X0_13") (pintype "bidirectional"))
      (node (ref "LED14") (pin "C") (pinfunction "C_C") (pintype "passive"))
      (node (ref "TSOP11") (pin "OUT") (pinfunction "OUT_OUT") (pintype "bidirectional"))
    )
    (net (code "71") (name "TSOP_12") (class "Default")
      (node (ref "IC3") (pin "1") (pinfunction "X4_1") (pintype "bidirectional"))
      (node (ref "LED15") (pin "C") (pinfunction "C_C") (pintype "passive"))
      (node (ref "TSOP12") (pin "OUT") (pinfunction "OUT_OUT") (pintype "bidirectional"))
    )
    (net (code "72") (name "TSOP_13") (class "Default")
      (node (ref "IC3") (pin "12") (pinfunction "X3_12") (pintype "bidirectional"))
      (node (ref "LED16") (pin "C") (pinfunction "C_C") (pintype "passive"))
      (node (ref "TSOP13") (pin "OUT") (pinfunction "OUT_OUT") (pintype "bidirectional"))
    )
    (net (code "73") (name "TSOP_14") (class "Default")
      (node (ref "IC4") (pin "1") (pinfunction "X4_1") (pintype "bidirectional"))
      (node (ref "LED17") (pin "C") (pinfunction "C_C") (pintype "passive"))
      (node (ref "TSOP14") (pin "OUT") (pinfunction "OUT_OUT") (pintype "bidirectional"))
    )
    (net (code "74") (name "TSOP_15") (class "Default")
      (node (ref "IC4") (pin "12") (pinfunction "X3_12") (pintype "bidirectional"))
      (node (ref "LED18") (pin "C") (pinfunction "C_C") (pintype "passive"))
      (node (ref "TSOP15") (pin "OUT") (pinfunction "OUT_OUT") (pintype "bidirectional"))
    )
    (net (code "75") (name "UART0_RX") (class "Default")
      (node (ref "IC5") (pin "2") (pinfunction "(RXD0/PDI)PE0_2") (pintype "bidirectional"))
      (node (ref "R1") (pin "2") (pinfunction "2_2") (pintype "passive"))
      (node (ref "X5") (pin "3") (pinfunction "S_3") (pintype "passive"))
    )
    (net (code "76") (name "UART1_RX") (class "Default")
      (node (ref "IC3") (pin "3") (pinfunction "X_3") (pintype "bidirectional"))
      (node (ref "IC5") (pin "27") (pinfunction "(RXD1/INT2)PD2_27") (pintype "bidirectional"))
      (node (ref "X4") (pin "2") (pinfunction "S_2") (pintype "passive"))
    )
    (net (code "77") (name "UART1_TX") (class "Default")
      (node (ref "IC5") (pin "28") (pinfunction "(TXD1/INT3)PD3_28") (pintype "bidirectional"))
      (node (ref "X4") (pin "3") (pinfunction "S_3") (pintype "passive"))
    )
    (net (code "78") (name "unconnected-(IC5-(A8)PC0-Pad35)") (class "Default")
      (node (ref "IC5") (pin "35") (pinfunction "(A8)PC0_35") (pintype "output"))
    )
    (net (code "79") (name "unconnected-(IC5-(A9)PC1-Pad36)") (class "Default")
      (node (ref "IC5") (pin "36") (pinfunction "(A9)PC1_36") (pintype "output"))
    )
    (net (code "80") (name "unconnected-(IC5-(A10)PC2-Pad37)") (class "Default")
      (node (ref "IC5") (pin "37") (pinfunction "(A10)PC2_37") (pintype "output"))
    )
    (net (code "81") (name "unconnected-(IC5-(A11)PC3-Pad38)") (class "Default")
      (node (ref "IC5") (pin "38") (pinfunction "(A11)PC3_38") (pintype "output"))
    )
    (net (code "82") (name "unconnected-(IC5-(A12)PC4-Pad39)") (class "Default")
      (node (ref "IC5") (pin "39") (pinfunction "(A12)PC4_39") (pintype "output"))
    )
    (net (code "83") (name "unconnected-(IC5-(A13)PC5-Pad40)") (class "Default")
      (node (ref "IC5") (pin "40") (pinfunction "(A13)PC5_40") (pintype "output"))
    )
    (net (code "84") (name "unconnected-(IC5-(A14)PC6-Pad41)") (class "Default")
      (node (ref "IC5") (pin "41") (pinfunction "(A14)PC6_41") (pintype "output"))
    )
    (net (code "85") (name "unconnected-(IC5-(AD0)PA0-Pad51)") (class "Default")
      (node (ref "IC5") (pin "51") (pinfunction "(AD0)PA0_51") (pintype "bidirectional"))
    )
    (net (code "86") (name "unconnected-(IC5-(AD1)PA1-Pad50)") (class "Default")
      (node (ref "IC5") (pin "50") (pinfunction "(AD1)PA1_50") (pintype "bidirectional"))
    )
    (net (code "87") (name "unconnected-(IC5-(AD2)PA2-Pad49)") (class "Default")
      (node (ref "IC5") (pin "49") (pinfunction "(AD2)PA2_49") (pintype "bidirectional"))
    )
    (net (code "88") (name "unconnected-(IC5-(AD7)PA7-Pad44)") (class "Default")
      (node (ref "IC5") (pin "44") (pinfunction "(AD7)PA7_44") (pintype "bidirectional"))
    )
    (net (code "89") (name "unconnected-(IC5-(CLKO{slash}A15)PC7-Pad42)") (class "Default")
      (node (ref "IC5") (pin "42") (pinfunction "(CLKO/A15)PC7_42") (pintype "output"))
    )
    (net (code "90") (name "unconnected-(IC5-(IC3{slash}INT7)PE7-Pad9)") (class "Default")
      (node (ref "IC5") (pin "9") (pinfunction "(IC3/INT7)PE7_9") (pintype "bidirectional"))
    )
    (net (code "91") (name "unconnected-(IC5-(ICP1)PD4-Pad29)") (class "Default")
      (node (ref "IC5") (pin "29") (pinfunction "(ICP1)PD4_29") (pintype "bidirectional"))
    )
    (net (code "92") (name "unconnected-(IC5-(MISO)PB3-Pad13)") (class "Default")
      (node (ref "IC5") (pin "13") (pinfunction "(MISO)PB3_13") (pintype "bidirectional"))
    )
    (net (code "93") (name "unconnected-(IC5-(MOSI)PB2-Pad12)") (class "Default")
      (node (ref "IC5") (pin "12") (pinfunction "(MOSI)PB2_12") (pintype "bidirectional"))
    )
    (net (code "94") (name "unconnected-(IC5-(OC0A{slash}OC1C)PB7-Pad17)") (class "Default")
      (node (ref "IC5") (pin "17") (pinfunction "(OC0A/OC1C)PB7_17") (pintype "bidirectional"))
    )
    (net (code "95") (name "unconnected-(IC5-(OC1A)PB5-Pad15)") (class "Default")
      (node (ref "IC5") (pin "15") (pinfunction "(OC1A)PB5_15") (pintype "bidirectional"))
    )
    (net (code "96") (name "unconnected-(IC5-(OC2A)PB4-Pad14)") (class "Default")
      (node (ref "IC5") (pin "14") (pinfunction "(OC2A)PB4_14") (pintype "bidirectional"))
    )
    (net (code "97") (name "unconnected-(IC5-(SCL{slash}INT0)PD0-Pad25)") (class "Default")
      (node (ref "IC5") (pin "25") (pinfunction "(SCL/INT0)PD0_25") (pintype "bidirectional"))
    )
    (net (code "98") (name "unconnected-(IC5-(SDA{slash}INT1)PD1-Pad26)") (class "Default")
      (node (ref "IC5") (pin "26") (pinfunction "(SDA/INT1)PD1_26") (pintype "bidirectional"))
    )
    (net (code "99") (name "unconnected-(IC5-(SS)PB0-Pad10)") (class "Default")
      (node (ref "IC5") (pin "10") (pinfunction "(SS)PB0_10") (pintype "bidirectional"))
    )
    (net (code "100") (name "unconnected-(IC5-(T2)PD7-Pad32)") (class "Default")
      (node (ref "IC5") (pin "32") (pinfunction "(T2)PD7_32") (pintype "bidirectional"))
    )
    (net (code "101") (name "unconnected-(IC5-(T3{slash}INT6)PE6-Pad8)") (class "Default")
      (node (ref "IC5") (pin "8") (pinfunction "(T3/INT6)PE6_8") (pintype "bidirectional"))
    )
    (net (code "102") (name "unconnected-(IC5-NC-Pad1)") (class "Default")
      (node (ref "IC5") (pin "1") (pinfunction "NC_1") (pintype "no_connect"))
    )
    (net (code "103") (name "unconnected-(IC5-PF0(ADC0)-Pad61)") (class "Default")
      (node (ref "IC5") (pin "61") (pinfunction "PF0(ADC0)_61") (pintype "input"))
    )
    (net (code "104") (name "unconnected-(IC5-PF1(ADC1)-Pad60)") (class "Default")
      (node (ref "IC5") (pin "60") (pinfunction "PF1(ADC1)_60") (pintype "input"))
    )
    (net (code "105") (name "unconnected-(IC5-PF2(ADC2)-Pad59)") (class "Default")
      (node (ref "IC5") (pin "59") (pinfunction "PF2(ADC2)_59") (pintype "input"))
    )
    (net (code "106") (name "unconnected-(IC5-PF3(ADC3)-Pad58)") (class "Default")
      (node (ref "IC5") (pin "58") (pinfunction "PF3(ADC3)_58") (pintype "input"))
    )
    (net (code "107") (name "unconnected-(IC5-PF4(ADC4{slash}TCK)-Pad57)") (class "Default")
      (node (ref "IC5") (pin "57") (pinfunction "PF4(ADC4/TCK)_57") (pintype "input"))
    )
    (net (code "108") (name "unconnected-(IC5-PF5(ADC5{slash}TMS)-Pad56)") (class "Default")
      (node (ref "IC5") (pin "56") (pinfunction "PF5(ADC5/TMS)_56") (pintype "input"))
    )
    (net (code "109") (name "unconnected-(IC5-PF6(ADC6{slash}TDO)-Pad55)") (class "Default")
      (node (ref "IC5") (pin "55") (pinfunction "PF6(ADC6/TDO)_55") (pintype "input"))
    )
    (net (code "110") (name "unconnected-(IC5-PF7(ADC7{slash}TDI)-Pad54)") (class "Default")
      (node (ref "IC5") (pin "54") (pinfunction "PF7(ADC7/TDI)_54") (pintype "input"))
    )
    (net (code "111") (name "unconnected-(IC5-PG0(WR)-Pad33)") (class "Default")
      (node (ref "IC5") (pin "33") (pinfunction "PG0(WR)_33") (pintype "bidirectional"))
    )
    (net (code "112") (name "unconnected-(IC5-PG1(RD)-Pad34)") (class "Default")
      (node (ref "IC5") (pin "34") (pinfunction "PG1(RD)_34") (pintype "bidirectional"))
    )
    (net (code "113") (name "unconnected-(IC5-PG2(ALE)-Pad43)") (class "Default")
      (node (ref "IC5") (pin "43") (pinfunction "PG2(ALE)_43") (pintype "bidirectional"))
    )
    (net (code "114") (name "unconnected-(IC5-PG3(TOSC2)-Pad18)") (class "Default")
      (node (ref "IC5") (pin "18") (pinfunction "PG3(TOSC2)_18") (pintype "bidirectional"))
    )
    (net (code "115") (name "unconnected-(IC5-PG4(TOSC1)-Pad19)") (class "Default")
      (node (ref "IC5") (pin "19") (pinfunction "PG4(TOSC1)_19") (pintype "bidirectional"))
    )
  )
)
